# SH6_-_PCIe_ETHERNET.net
KiCad netlist of a schematic drawn in Altium Designer
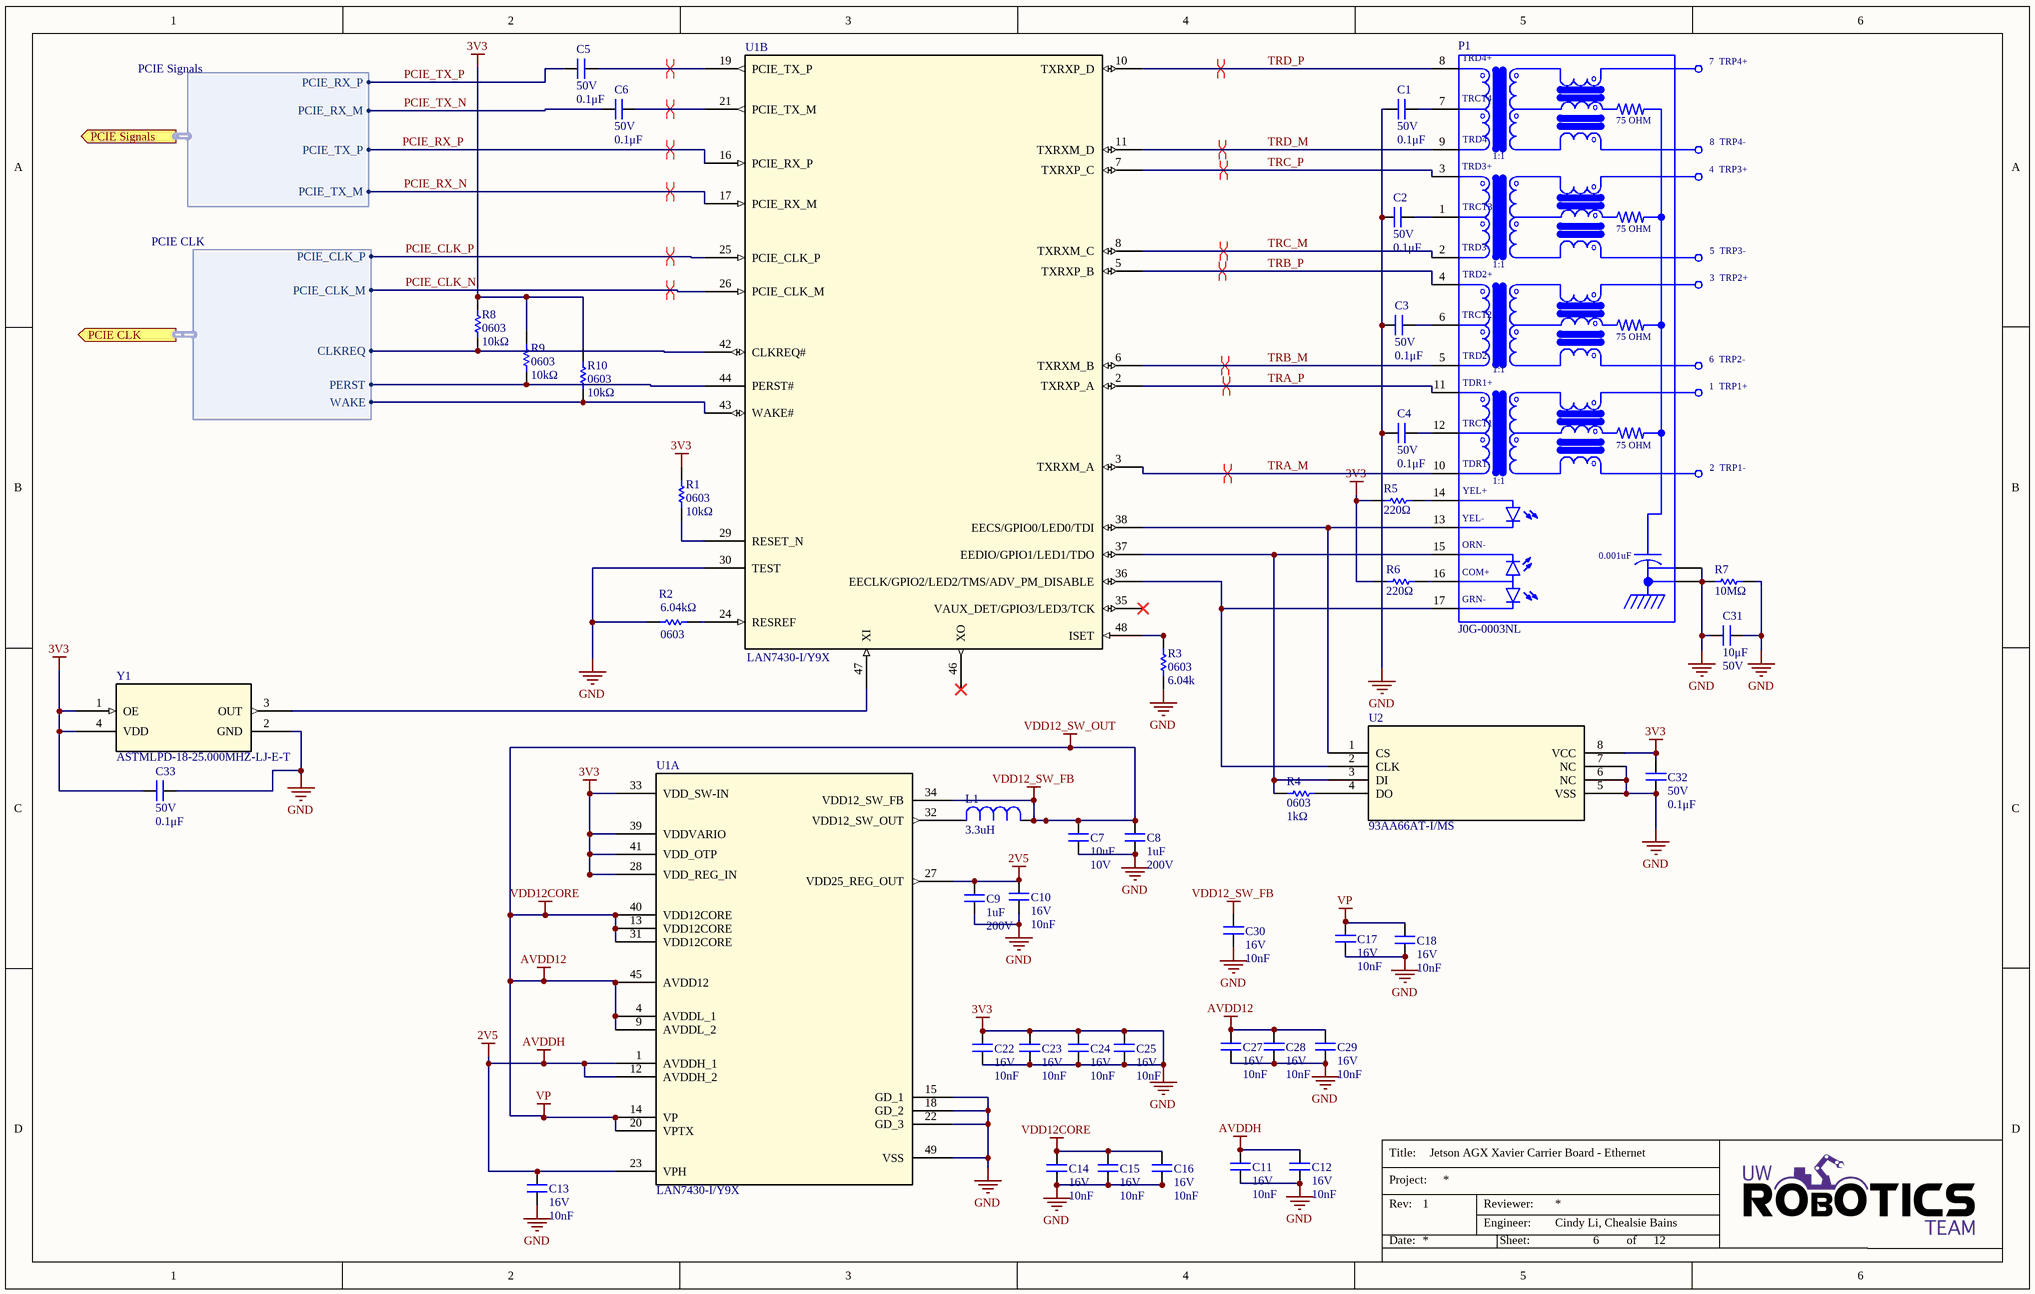
[diagram p0: SH6 - PCIe ETHERNET.SchDoc]

(export (version "E")
  (design (tool "Eeschema 10.0.6"))
  (components
    (comp (ref "C1")
      (value "0.1μF")
      (footprint "CAP0603")
      (description "CAP CER 0.1UF 50V X7R 0603")
      (fields (field (name "VOLTAGE RATING") "50V") (field (name "Comment") "CAP_0.1uF_50V_0603"))
      (libsource (lib "UWRT_Schematic_Library_2020") (part "CAP_0.1uF_50V_0603"))
    )
    (comp (ref "C2")
      (value "0.1μF")
      (footprint "CAP0603")
      (description "CAP CER 0.1UF 50V X7R 0603")
      (fields (field (name "VOLTAGE RATING") "50V") (field (name "Comment") "CAP_0.1uF_50V_0603"))
      (libsource (lib "UWRT_Schematic_Library_2020") (part "CAP_0.1uF_50V_0603"))
    )
    (comp (ref "C3")
      (value "0.1μF")
      (footprint "CAP0603")
      (description "CAP CER 0.1UF 50V X7R 0603")
      (fields (field (name "VOLTAGE RATING") "50V") (field (name "Comment") "CAP_0.1uF_50V_0603"))
      (libsource (lib "UWRT_Schematic_Library_2020") (part "CAP_0.1uF_50V_0603"))
    )
    (comp (ref "C4")
      (value "0.1μF")
      (footprint "CAP0603")
      (description "CAP CER 0.1UF 50V X7R 0603")
      (fields (field (name "VOLTAGE RATING") "50V") (field (name "Comment") "CAP_0.1uF_50V_0603"))
      (libsource (lib "UWRT_Schematic_Library_2020") (part "CAP_0.1uF_50V_0603"))
    )
    (comp (ref "C5")
      (value "0.1μF")
      (footprint "CAP0603")
      (description "CAP CER 0.1UF 50V X7R 0603")
      (fields (field (name "VOLTAGE RATING") "50V") (field (name "Comment") "CAP_0.1uF_50V_0603"))
      (libsource (lib "UWRT_Schematic_Library_2020") (part "CAP_0.1uF_50V_0603"))
    )
    (comp (ref "C6")
      (value "0.1μF")
      (footprint "CAP0603")
      (description "CAP CER 0.1UF 50V X7R 0603")
      (fields (field (name "VOLTAGE RATING") "50V") (field (name "Comment") "CAP_0.1uF_50V_0603"))
      (libsource (lib "UWRT_Schematic_Library_2020") (part "CAP_0.1uF_50V_0603"))
    )
    (comp (ref "C7")
      (value "10uF")
      (fields
        (field (name "MANUFACTURER") "Taiyo Yuden")
        (field (name "MANUFACTURER PART NUMBER") "LMK212AC6106MD-T")
        (field (name "VOLTAGE") "10V")
        (field (name "Comment") "CAP CER 10UF 10V X6S 0805")
      )
      (libsource (lib "UWRT_Schematic_Library_2020") (part "CAP CER 10UF 10V X6S 0805"))
    )
    (comp (ref "C8")
      (value "1uF")
      (footprint "CAP_CER_10000PF")
      (fields
        (field (name "MANUFACTURER") "Taiyo Yuden")
        (field (name "MANUFACTURER PART NUMBER") "GMK107BJ105MAHT")
        (field (name "VOLTAGE RATING") "200V")
        (field (name "Comment") "CAP_1uF_200V_0603")
      )
      (libsource (lib "UWRT_Schematic_Library_2020") (part "CAP_1uF_200V_0603"))
    )
    (comp (ref "C9")
      (value "1uF")
      (footprint "CAP_CER_10000PF")
      (fields
        (field (name "MANUFACTURER") "Taiyo Yuden")
        (field (name "MANUFACTURER PART NUMBER") "GMK107BJ105MAHT")
        (field (name "VOLTAGE RATING") "200V")
        (field (name "Comment") "CAP_1uF_200V_0603")
      )
      (libsource (lib "UWRT_Schematic_Library_2020") (part "CAP_1uF_200V_0603"))
    )
    (comp (ref "C10")
      (value "10nF")
      (footprint "CAP2012")
      (description "CAP CER 10000PF 16V X7R 0805")
      (fields (field (name "VOLTAGE RATING") "16V") (field (name "Comment") "CAP_10nF_16V_0805"))
      (libsource (lib "UWRT_Schematic_Library_2020") (part "CAP_10nF_16V_0805"))
    )
    (comp (ref "C11")
      (value "10nF")
      (footprint "CAP2012")
      (description "CAP CER 10000PF 16V X7R 0805")
      (fields (field (name "VOLTAGE RATING") "16V") (field (name "Comment") "CAP_10nF_16V_0805"))
      (libsource (lib "UWRT_Schematic_Library_2020") (part "CAP_10nF_16V_0805"))
    )
    (comp (ref "C12")
      (value "10nF")
      (footprint "CAP2012")
      (description "CAP CER 10000PF 16V X7R 0805")
      (fields (field (name "VOLTAGE RATING") "16V") (field (name "Comment") "CAP_10nF_16V_0805"))
      (libsource (lib "UWRT_Schematic_Library_2020") (part "CAP_10nF_16V_0805"))
    )
    (comp (ref "C13")
      (value "10nF")
      (footprint "CAP2012")
      (description "CAP CER 10000PF 16V X7R 0805")
      (fields (field (name "VOLTAGE RATING") "16V") (field (name "Comment") "CAP_10nF_16V_0805"))
      (libsource (lib "UWRT_Schematic_Library_2020") (part "CAP_10nF_16V_0805"))
    )
    (comp (ref "C14")
      (value "10nF")
      (footprint "CAP2012")
      (description "CAP CER 10000PF 16V X7R 0805")
      (fields (field (name "VOLTAGE RATING") "16V") (field (name "Comment") "CAP_10nF_16V_0805"))
      (libsource (lib "UWRT_Schematic_Library_2020") (part "CAP_10nF_16V_0805"))
    )
    (comp (ref "C15")
      (value "10nF")
      (footprint "CAP2012")
      (description "CAP CER 10000PF 16V X7R 0805")
      (fields (field (name "VOLTAGE RATING") "16V") (field (name "Comment") "CAP_10nF_16V_0805"))
      (libsource (lib "UWRT_Schematic_Library_2020") (part "CAP_10nF_16V_0805"))
    )
    (comp (ref "C16")
      (value "10nF")
      (footprint "CAP2012")
      (description "CAP CER 10000PF 16V X7R 0805")
      (fields (field (name "VOLTAGE RATING") "16V") (field (name "Comment") "CAP_10nF_16V_0805"))
      (libsource (lib "UWRT_Schematic_Library_2020") (part "CAP_10nF_16V_0805"))
    )
    (comp (ref "C17")
      (value "10nF")
      (footprint "CAP2012")
      (description "CAP CER 10000PF 16V X7R 0805")
      (fields (field (name "VOLTAGE RATING") "16V") (field (name "Comment") "CAP_10nF_16V_0805"))
      (libsource (lib "UWRT_Schematic_Library_2020") (part "CAP_10nF_16V_0805"))
    )
    (comp (ref "C18")
      (value "10nF")
      (footprint "CAP2012")
      (description "CAP CER 10000PF 16V X7R 0805")
      (fields (field (name "VOLTAGE RATING") "16V") (field (name "Comment") "CAP_10nF_16V_0805"))
      (libsource (lib "UWRT_Schematic_Library_2020") (part "CAP_10nF_16V_0805"))
    )
    (comp (ref "C22")
      (value "10nF")
      (footprint "CAP2012")
      (description "CAP CER 10000PF 16V X7R 0805")
      (fields (field (name "VOLTAGE RATING") "16V") (field (name "Comment") "CAP_10nF_16V_0805"))
      (libsource (lib "UWRT_Schematic_Library_2020") (part "CAP_10nF_16V_0805"))
    )
    (comp (ref "C23")
      (value "10nF")
      (footprint "CAP2012")
      (description "CAP CER 10000PF 16V X7R 0805")
      (fields (field (name "VOLTAGE RATING") "16V") (field (name "Comment") "CAP_10nF_16V_0805"))
      (libsource (lib "UWRT_Schematic_Library_2020") (part "CAP_10nF_16V_0805"))
    )
    (comp (ref "C24")
      (value "10nF")
      (footprint "CAP2012")
      (description "CAP CER 10000PF 16V X7R 0805")
      (fields (field (name "VOLTAGE RATING") "16V") (field (name "Comment") "CAP_10nF_16V_0805"))
      (libsource (lib "UWRT_Schematic_Library_2020") (part "CAP_10nF_16V_0805"))
    )
    (comp (ref "C25")
      (value "10nF")
      (footprint "CAP2012")
      (description "CAP CER 10000PF 16V X7R 0805")
      (fields (field (name "VOLTAGE RATING") "16V") (field (name "Comment") "CAP_10nF_16V_0805"))
      (libsource (lib "UWRT_Schematic_Library_2020") (part "CAP_10nF_16V_0805"))
    )
    (comp (ref "C27")
      (value "10nF")
      (footprint "CAP2012")
      (description "CAP CER 10000PF 16V X7R 0805")
      (fields (field (name "VOLTAGE RATING") "16V") (field (name "Comment") "CAP_10nF_16V_0805"))
      (libsource (lib "UWRT_Schematic_Library_2020") (part "CAP_10nF_16V_0805"))
    )
    (comp (ref "C28")
      (value "10nF")
      (footprint "CAP2012")
      (description "CAP CER 10000PF 16V X7R 0805")
      (fields (field (name "VOLTAGE RATING") "16V") (field (name "Comment") "CAP_10nF_16V_0805"))
      (libsource (lib "UWRT_Schematic_Library_2020") (part "CAP_10nF_16V_0805"))
    )
    (comp (ref "C29")
      (value "10nF")
      (footprint "CAP2012")
      (description "CAP CER 10000PF 16V X7R 0805")
      (fields (field (name "VOLTAGE RATING") "16V") (field (name "Comment") "CAP_10nF_16V_0805"))
      (libsource (lib "UWRT_Schematic_Library_2020") (part "CAP_10nF_16V_0805"))
    )
    (comp (ref "C30")
      (value "10nF")
      (footprint "CAP2012")
      (description "CAP CER 10000PF 16V X7R 0805")
      (fields (field (name "VOLTAGE RATING") "16V") (field (name "Comment") "CAP_10nF_16V_0805"))
      (libsource (lib "UWRT_Schematic_Library_2020") (part "CAP_10nF_16V_0805"))
    )
    (comp (ref "C31")
      (value "10μF")
      (footprint "CAP1206")
      (description "CAP CER 10UF 50V X5R 1206")
      (fields (field (name "VOLTAGE RATING") "50V") (field (name "Comment") "CAP_10uF_50V_1206"))
      (libsource (lib "UWRT_Schematic_Library_2020") (part "CAP_10uF_50V_1206"))
    )
    (comp (ref "C32")
      (value "0.1μF")
      (footprint "CAP0603")
      (description "CAP CER 0.1UF 50V X7R 0603")
      (fields (field (name "VOLTAGE RATING") "50V") (field (name "Comment") "CAP_0.1uF_50V_0603"))
      (libsource (lib "UWRT_Schematic_Library_2020") (part "CAP_0.1uF_50V_0603"))
    )
    (comp (ref "C33")
      (value "0.1μF")
      (footprint "CAP0603")
      (description "CAP CER 0.1UF 50V X7R 0603")
      (fields (field (name "VOLTAGE RATING") "50V") (field (name "Comment") "CAP_0.1uF_50V_0603"))
      (libsource (lib "UWRT_Schematic_Library_2020") (part "CAP_0.1uF_50V_0603"))
    )
    (comp (ref "L1")
      (value "IND_3.3uH")
      (footprint "IND_BOURNS_SRN6045")
      (description "FIXED INDUCTOR 3.3UH SMD")
      (fields (field (name "INDUCTANCE") "3.3uH"))
      (libsource (lib "UWRT_Schematic_Library_2020") (part "IND_3.3uH"))
    )
    (comp (ref "P1")
      (value "J0G-0003NL")
      (footprint "SnapEDApcb:PULSE_J0G-0003NL")
      (description "1 Port RJ45 Magjack Connector Through Hole 10/100/1000 Base-T, AutoMDIX")
      (fields (field (name "DIGI-KEY_PART_NUMBER") "553-1852-ND") (field (name "MF") "Pulse Electronics"))
      (libsource (lib "UWRT_Schematic_Library_2020") (part "J0G-0003NL"))
    )
    (comp (ref "R1")
      (value "10kΩ")
      (footprint "RESC0603")
      (description "RES 10K OHM 5% 1/10W 0603")
      (fields (field (name "PACKAGE/FOOTPRINT") "0603") (field (name "Comment") "RES_10kΩ_0603_5%"))
      (libsource (lib "UWRT_Schematic_Library_2020") (part "RES_10kΩ_0603_5%"))
    )
    (comp (ref "R2")
      (value "~")
      (footprint "RESC1608X55N:RESC1608X55N")
      (description "RES 0603 200 OHM 1/10W 1% SMD")
      (fields (field (name "MP") "SFR03EZPF2000"))
      (libsource (lib "UWRT_Schematic_Library_2020") (part "RES_200Ω"))
    )
    (comp (ref "R3")
      (value "6.04k")
      (footprint "RES0603")
      (description "RES 6.04K OHM 1% 1/10W 0603")
      (fields (field (name "PACKAGE/FOOTPRINT") "0603") (field (name "Comment") "RES_6.04kΩ_0603_1%"))
      (libsource (lib "UWRT_Schematic_Library_2020") (part "RES_6.04kΩ_0603_1%"))
    )
    (comp (ref "R4")
      (value "1kΩ")
      (footprint "RESC0603")
      (description "RES 1K OHM 5% 1/10W 0603")
      (fields (field (name "PACKAGE/FOOTPRINT") "0603") (field (name "Comment") "RES_1kΩ_0603_5%"))
      (libsource (lib "UWRT_Schematic_Library_2020") (part "RES_1kΩ_0603_5%"))
    )
    (comp (ref "R5")
      (value "220Ω")
      (footprint "RESC0603")
      (description "RES 220 OHM 5% 1/10W 0603")
      (fields (field (name "Comment") "RES_220Ω_0603"))
      (libsource (lib "UWRT_Schematic_Library_2020") (part "RES_220Ω_0603_5%"))
    )
    (comp (ref "R6")
      (value "220Ω")
      (footprint "RESC0603")
      (description "RES 220 OHM 5% 1/10W 0603")
      (fields (field (name "Comment") "RES_220Ω_0603"))
      (libsource (lib "UWRT_Schematic_Library_2020") (part "RES_220Ω_0603_5%"))
    )
    (comp (ref "R7")
      (value "10MΩ")
      (footprint "RES0603")
      (description "RES 10M OHM 5% 1/10W 0603")
      (fields (field (name "Comment") "RES_10MΩ_0603"))
      (libsource (lib "UWRT_Schematic_Library_2020") (part "RES_10MΩ_0603_5%"))
    )
    (comp (ref "R8")
      (value "10kΩ")
      (footprint "RES0603")
      (description "RES 10K OHM 5% 1/10W 0603")
      (fields (field (name "PACKAGE/FOOTPRINT") "0603") (field (name "Comment") "RES_10kΩ_0603_5%"))
      (libsource (lib "UWRT_Schematic_Library_2020") (part "RES_10kΩ_0603_5%"))
    )
    (comp (ref "R9")
      (value "10kΩ")
      (footprint "RES0603")
      (description "RES 10K OHM 5% 1/10W 0603")
      (fields (field (name "PACKAGE/FOOTPRINT") "0603") (field (name "Comment") "RES_10kΩ_0603_5%"))
      (libsource (lib "UWRT_Schematic_Library_2020") (part "RES_10kΩ_0603_5%"))
    )
    (comp (ref "R10")
      (value "10kΩ")
      (footprint "RES0603")
      (description "RES 10K OHM 5% 1/10W 0603")
      (fields (field (name "PACKAGE/FOOTPRINT") "0603") (field (name "Comment") "RES_10kΩ_0603_5%"))
      (libsource (lib "UWRT_Schematic_Library_2020") (part "RES_10kΩ_0603_5%"))
    )
    (comp (ref "U1")
      (value "LAN7430-I/Y9X")
      (footprint "SQFN48_MCH")
      (fields (field (name "COPYRIGHT") "Copyright (C) 2018 Accelerated Designs. All rights reserved"))
      (libsource (lib "UWRT_Schematic_Library_2020") (part "LAN7430-I/Y9X"))
    )
    (comp (ref "U2")
      (value "93AA66AT-I/MS")
      (footprint "MSOP8_MC_MCH")
      (description "No Description Available")
      (fields (field (name "COPYRIGHT") "Copyright (C) 2018 Accelerated Designs. All rights reserved"))
      (libsource (lib "UWRT_Schematic_Library_2020") (part "93AA66AT-I/MS"))
    )
    (comp (ref "Y1")
      (value "ASTMLPD-18-25.000MHZ-LJ-E-T")
      (footprint "ASTMLPE_ABR")
      (description "Oscillator")
      (libsource (lib "UWRT_Schematic_Library_2020") (part "ASTMLPD-18-25.000MHZ-LJ-E-T"))
    )
  )
  (nets
    (net (code "4") (name "/PCIE_CLK_N") (class "Default")
      (node (ref "U1") (pin "26") (pinfunction "PCIE_CLK_M_26") (pintype "input"))
    )
    (net (code "5") (name "/PCIE_CLK_P") (class "Default")
      (node (ref "U1") (pin "25") (pinfunction "PCIE_CLK_P_25") (pintype "input"))
    )
    (net (code "6") (name "/PCIE_RX_N") (class "Default")
      (node (ref "U1") (pin "17") (pinfunction "PCIE_RX_M_17") (pintype "input"))
    )
    (net (code "7") (name "/PCIE_RX_P") (class "Default")
      (node (ref "U1") (pin "16") (pinfunction "PCIE_RX_P_16") (pintype "input"))
    )
    (net (code "8") (name "/PCIE_TX_N") (class "Default")
      (node (ref "C6") (pin "1") (pinfunction "1_1") (pintype "passive"))
    )
    (net (code "9") (name "/PCIE_TX_P") (class "Default")
      (node (ref "C5") (pin "1") (pinfunction "1_1") (pintype "passive"))
    )
    (net (code "10") (name "/TRA_M") (class "Default")
      (node (ref "P1") (pin "10") (pinfunction "TDR1-_10") (pintype "passive"))
      (node (ref "U1") (pin "3") (pinfunction "TXRXM_A_3") (pintype "bidirectional"))
    )
    (net (code "11") (name "/TRA_P") (class "Default")
      (node (ref "P1") (pin "11") (pinfunction "TDR1+_11") (pintype "passive"))
      (node (ref "U1") (pin "2") (pinfunction "TXRXP_A_2") (pintype "bidirectional"))
    )
    (net (code "12") (name "/TRB_M") (class "Default")
      (node (ref "P1") (pin "5") (pinfunction "TRD2-_5") (pintype "passive"))
      (node (ref "U1") (pin "6") (pinfunction "TXRXM_B_6") (pintype "bidirectional"))
    )
    (net (code "13") (name "/TRB_P") (class "Default")
      (node (ref "P1") (pin "4") (pinfunction "TRD2+_4") (pintype "passive"))
      (node (ref "U1") (pin "5") (pinfunction "TXRXP_B_5") (pintype "bidirectional"))
    )
    (net (code "14") (name "/TRC_M") (class "Default")
      (node (ref "P1") (pin "2") (pinfunction "TRD3-_2") (pintype "passive"))
      (node (ref "U1") (pin "8") (pinfunction "TXRXM_C_8") (pintype "bidirectional"))
    )
    (net (code "15") (name "/TRC_P") (class "Default")
      (node (ref "P1") (pin "3") (pinfunction "TRD3+_3") (pintype "passive"))
      (node (ref "U1") (pin "7") (pinfunction "TXRXP_C_7") (pintype "bidirectional"))
    )
    (net (code "16") (name "/TRD_M") (class "Default")
      (node (ref "P1") (pin "9") (pinfunction "TRD4-_9") (pintype "passive"))
      (node (ref "U1") (pin "11") (pinfunction "TXRXM_D_11") (pintype "bidirectional"))
    )
    (net (code "17") (name "/TRD_P") (class "Default")
      (node (ref "P1") (pin "8") (pinfunction "TRD4+_8") (pintype "passive"))
      (node (ref "U1") (pin "10") (pinfunction "TXRXP_D_10") (pintype "bidirectional"))
    )
    (net (code "20") (name "2V5") (class "Default")
      (node (ref "C10") (pin "2") (pinfunction "2_2") (pintype "passive"))
      (node (ref "C11") (pin "2") (pinfunction "2_2") (pintype "passive"))
      (node (ref "C12") (pin "2") (pinfunction "2_2") (pintype "passive"))
      (node (ref "C13") (pin "2") (pinfunction "2_2") (pintype "passive"))
      (node (ref "C9") (pin "2") (pinfunction "2_2") (pintype "passive"))
      (node (ref "U1") (pin "1") (pinfunction "AVDDH_1_1") (pintype "power_in"))
      (node (ref "U1") (pin "12") (pinfunction "AVDDH_2_12") (pintype "power_in"))
      (node (ref "U1") (pin "23") (pinfunction "VPH_23") (pintype "power_in"))
      (node (ref "U1") (pin "27") (pinfunction "VDD25_REG_OUT_27") (pintype "output"))
    )
    (net (code "21") (name "3V3") (class "Default")
      (node (ref "C1") (pin "1") (pinfunction "1_1") (pintype "passive"))
      (node (ref "C10") (pin "1") (pinfunction "1_1") (pintype "passive"))
      (node (ref "C11") (pin "1") (pinfunction "1_1") (pintype "passive"))
      (node (ref "C12") (pin "1") (pinfunction "1_1") (pintype "passive"))
      (node (ref "C13") (pin "1") (pinfunction "1_1") (pintype "passive"))
      (node (ref "C14") (pin "1") (pinfunction "1_1") (pintype "passive"))
      (node (ref "C15") (pin "1") (pinfunction "1_1") (pintype "passive"))
      (node (ref "C16") (pin "1") (pinfunction "1_1") (pintype "passive"))
      (node (ref "C17") (pin "1") (pinfunction "1_1") (pintype "passive"))
      (node (ref "C18") (pin "1") (pinfunction "1_1") (pintype "passive"))
      (node (ref "C2") (pin "1") (pinfunction "1_1") (pintype "passive"))
      (node (ref "C22") (pin "1") (pinfunction "1_1") (pintype "passive"))
      (node (ref "C22") (pin "2") (pinfunction "2_2") (pintype "passive"))
      (node (ref "C23") (pin "1") (pinfunction "1_1") (pintype "passive"))
      (node (ref "C23") (pin "2") (pinfunction "2_2") (pintype "passive"))
      (node (ref "C24") (pin "1") (pinfunction "1_1") (pintype "passive"))
      (node (ref "C24") (pin "2") (pinfunction "2_2") (pintype "passive"))
      (node (ref "C25") (pin "1") (pinfunction "1_1") (pintype "passive"))
      (node (ref "C25") (pin "2") (pinfunction "2_2") (pintype "passive"))
      (node (ref "C27") (pin "1") (pinfunction "1_1") (pintype "passive"))
      (node (ref "C28") (pin "1") (pinfunction "1_1") (pintype "passive"))
      (node (ref "C29") (pin "1") (pinfunction "1_1") (pintype "passive"))
      (node (ref "C3") (pin "1") (pinfunction "1_1") (pintype "passive"))
      (node (ref "C30") (pin "1") (pinfunction "1_1") (pintype "passive"))
      (node (ref "C31") (pin "1") (pinfunction "1_1") (pintype "passive"))
      (node (ref "C31") (pin "2") (pinfunction "2_2") (pintype "passive"))
      (node (ref "C32") (pin "1") (pinfunction "1_1") (pintype "passive"))
      (node (ref "C32") (pin "2") (pinfunction "2_2") (pintype "passive"))
      (node (ref "C33") (pin "1") (pinfunction "1_1") (pintype "passive"))
      (node (ref "C33") (pin "2") (pinfunction "2_2") (pintype "passive"))
      (node (ref "C4") (pin "1") (pinfunction "1_1") (pintype "passive"))
      (node (ref "C7") (pin "1") (pinfunction "1_1") (pintype "passive"))
      (node (ref "C8") (pin "1") (pinfunction "1_1") (pintype "passive"))
      (node (ref "C9") (pin "1") (pinfunction "1_1") (pintype "passive"))
      (node (ref "P1") (pin "SH1") (pinfunction "SHIELD_SH1") (pintype "power_in"))
      (node (ref "P1") (pin "SH2") (pinfunction "SHIELD_SH2") (pintype "power_in"))
      (node (ref "R1") (pin "2") (pinfunction "2_2") (pintype "passive"))
      (node (ref "R10") (pin "2") (pinfunction "2_2") (pintype "passive"))
      (node (ref "R2") (pin "1") (pinfunction "1_1") (pintype "passive"))
      (node (ref "R3") (pin "2") (pinfunction "2_2") (pintype "passive"))
      (node (ref "R5") (pin "1") (pinfunction "1_1") (pintype "passive"))
      (node (ref "R6") (pin "1") (pinfunction "1_1") (pintype "passive"))
      (node (ref "R7") (pin "1") (pinfunction "1_1") (pintype "passive"))
      (node (ref "R7") (pin "2") (pinfunction "2_2") (pintype "passive"))
      (node (ref "R8") (pin "2") (pinfunction "2_2") (pintype "passive"))
      (node (ref "R9") (pin "2") (pinfunction "2_2") (pintype "passive"))
      (node (ref "U1") (pin "15") (pinfunction "GD_1_15") (pintype "power_in"))
      (node (ref "U1") (pin "18") (pinfunction "GD_2_18") (pintype "power_in"))
      (node (ref "U1") (pin "22") (pinfunction "GD_3_22") (pintype "power_in"))
      (node (ref "U1") (pin "28") (pinfunction "VDD_REG_IN_28") (pintype "power_in"))
      (node (ref "U1") (pin "30") (pinfunction "TEST_30") (pintype "passive"))
      (node (ref "U1") (pin "33") (pinfunction "VDD_SW-IN_33") (pintype "power_in"))
      (node (ref "U1") (pin "39") (pinfunction "VDDVARIO_39") (pintype "power_in"))
      (node (ref "U1") (pin "41") (pinfunction "VDD_OTP_41") (pintype "power_in"))
      (node (ref "U1") (pin "49") (pinfunction "VSS_49") (pintype "passive"))
      (node (ref "U2") (pin "5") (pinfunction "VSS_5") (pintype "passive"))
      (node (ref "U2") (pin "6") (pinfunction "NC_6") (pintype "passive"))
      (node (ref "U2") (pin "7") (pinfunction "NC_7") (pintype "passive"))
      (node (ref "U2") (pin "8") (pinfunction "VCC_8") (pintype "passive"))
      (node (ref "Y1") (pin "1") (pinfunction "OE_1") (pintype "input"))
      (node (ref "Y1") (pin "2") (pinfunction "GND_2") (pintype "passive"))
      (node (ref "Y1") (pin "4") (pinfunction "VDD_4") (pintype "power_in"))
    )
    (net (code "22") (name "AVDD12") (class "Default")
      (node (ref "C14") (pin "2") (pinfunction "2_2") (pintype "passive"))
      (node (ref "C15") (pin "2") (pinfunction "2_2") (pintype "passive"))
      (node (ref "C16") (pin "2") (pinfunction "2_2") (pintype "passive"))
      (node (ref "C17") (pin "2") (pinfunction "2_2") (pintype "passive"))
      (node (ref "C18") (pin "2") (pinfunction "2_2") (pintype "passive"))
      (node (ref "C27") (pin "2") (pinfunction "2_2") (pintype "passive"))
      (node (ref "C28") (pin "2") (pinfunction "2_2") (pintype "passive"))
      (node (ref "C29") (pin "2") (pinfunction "2_2") (pintype "passive"))
      (node (ref "C7") (pin "2") (pinfunction "2_2") (pintype "passive"))
      (node (ref "C8") (pin "2") (pinfunction "2_2") (pintype "passive"))
      (node (ref "L1") (pin "1") (pinfunction "1_1") (pintype "passive"))
      (node (ref "U1") (pin "13") (pinfunction "VDD12CORE_13") (pintype "power_in"))
      (node (ref "U1") (pin "14") (pinfunction "VP_14") (pintype "power_in"))
      (node (ref "U1") (pin "20") (pinfunction "VPTX_20") (pintype "power_in"))
      (node (ref "U1") (pin "31") (pinfunction "VDD12CORE_31") (pintype "power_in"))
      (node (ref "U1") (pin "34") (pinfunction "VDD12_SW_FB_34") (pintype "power_in"))
      (node (ref "U1") (pin "4") (pinfunction "AVDDL_1_4") (pintype "power_in"))
      (node (ref "U1") (pin "40") (pinfunction "VDD12CORE_40") (pintype "power_in"))
      (node (ref "U1") (pin "45") (pinfunction "AVDD12_45") (pintype "power_in"))
      (node (ref "U1") (pin "9") (pinfunction "AVDDL_2_9") (pintype "power_in"))
    )
    (net (code "23") (name "Net-(P1-COM+)") (class "Default")
      (node (ref "P1") (pin "16") (pinfunction "COM+_16") (pintype "passive"))
      (node (ref "R6") (pin "2") (pinfunction "2_2") (pintype "passive"))
    )
    (net (code "24") (name "Net-(P1-GRN-)") (class "Default")
      (node (ref "P1") (pin "17") (pinfunction "GRN-_17") (pintype "passive"))
      (node (ref "U1") (pin "36") (pinfunction "EECLK/GPIO2/LED2/TMS/ADV_PM_DISABLE_36") (pintype "bidirectional"))
      (node (ref "U2") (pin "2") (pinfunction "CLK_2") (pintype "passive"))
    )
    (net (code "25") (name "Net-(P1-ORN-)") (class "Default")
      (node (ref "P1") (pin "15") (pinfunction "ORN-_15") (pintype "passive"))
      (node (ref "R4") (pin "1") (pinfunction "1_1") (pintype "passive"))
      (node (ref "U1") (pin "37") (pinfunction "EEDIO/GPIO1/LED1/TDO_37") (pintype "bidirectional"))
      (node (ref "U2") (pin "3") (pinfunction "DI_3") (pintype "passive"))
    )
    (net (code "26") (name "Net-(P1-TRCT1)") (class "Default")
      (node (ref "C4") (pin "2") (pinfunction "2_2") (pintype "passive"))
      (node (ref "P1") (pin "12") (pinfunction "TRCT1_12") (pintype "passive"))
    )
    (net (code "27") (name "Net-(P1-TRCT2)") (class "Default")
      (node (ref "C3") (pin "2") (pinfunction "2_2") (pintype "passive"))
      (node (ref "P1") (pin "6") (pinfunction "TRCT2_6") (pintype "passive"))
    )
    (net (code "28") (name "Net-(P1-TRCT3)") (class "Default")
      (node (ref "C2") (pin "2") (pinfunction "2_2") (pintype "passive"))
      (node (ref "P1") (pin "1") (pinfunction "TRCT3_1") (pintype "passive"))
    )
    (net (code "29") (name "Net-(P1-TRCT4)") (class "Default")
      (node (ref "C1") (pin "2") (pinfunction "2_2") (pintype "passive"))
      (node (ref "P1") (pin "7") (pinfunction "TRCT4_7") (pintype "passive"))
    )
    (net (code "30") (name "Net-(P1-YEL+)") (class "Default")
      (node (ref "P1") (pin "14") (pinfunction "YEL+_14") (pintype "passive"))
      (node (ref "R5") (pin "2") (pinfunction "2_2") (pintype "passive"))
    )
    (net (code "31") (name "Net-(P1-YEL-)") (class "Default")
      (node (ref "P1") (pin "13") (pinfunction "YEL-_13") (pintype "passive"))
      (node (ref "U1") (pin "38") (pinfunction "EECS/GPIO0/LED0/TDI_38") (pintype "bidirectional"))
      (node (ref "U2") (pin "1") (pinfunction "CS_1") (pintype "passive"))
    )
    (net (code "32") (name "Net-(U1A-VDD12_SW_OUT)") (class "Default")
      (node (ref "L1") (pin "2") (pinfunction "2_2") (pintype "passive"))
      (node (ref "U1") (pin "32") (pinfunction "VDD12_SW_OUT_32") (pintype "output"))
    )
    (net (code "33") (name "Net-(U1B-CLKREQ#)") (class "Default")
      (node (ref "R8") (pin "1") (pinfunction "1_1") (pintype "passive"))
      (node (ref "U1") (pin "42") (pinfunction "CLKREQ#_42") (pintype "bidirectional"))
    )
    (net (code "34") (name "Net-(U1B-ISET)") (class "Default")
      (node (ref "R3") (pin "1") (pinfunction "1_1") (pintype "passive"))
      (node (ref "U1") (pin "48") (pinfunction "ISET_48") (pintype "input"))
    )
    (net (code "35") (name "Net-(U1B-PCIE_TX_M)") (class "Default")
      (node (ref "C6") (pin "2") (pinfunction "2_2") (pintype "passive"))
      (node (ref "U1") (pin "21") (pinfunction "PCIE_TX_M_21") (pintype "output"))
    )
    (net (code "36") (name "Net-(U1B-PCIE_TX_P)") (class "Default")
      (node (ref "C5") (pin "2") (pinfunction "2_2") (pintype "passive"))
      (node (ref "U1") (pin "19") (pinfunction "PCIE_TX_P_19") (pintype "output"))
    )
    (net (code "37") (name "Net-(U1B-PERST#)") (class "Default")
      (node (ref "R9") (pin "1") (pinfunction "1_1") (pintype "passive"))
      (node (ref "U1") (pin "44") (pinfunction "PERST#_44") (pintype "passive"))
    )
    (net (code "38") (name "Net-(U1B-RESET_N)") (class "Default")
      (node (ref "R1") (pin "1") (pinfunction "1_1") (pintype "passive"))
      (node (ref "U1") (pin "29") (pinfunction "RESET_N_29") (pintype "passive"))
    )
    (net (code "39") (name "Net-(U1B-RESREF)") (class "Default")
      (node (ref "R2") (pin "2") (pinfunction "2_2") (pintype "passive"))
      (node (ref "U1") (pin "24") (pinfunction "RESREF_24") (pintype "input"))
    )
    (net (code "40") (name "Net-(U1B-WAKE#)") (class "Default")
      (node (ref "R10") (pin "1") (pinfunction "1_1") (pintype "passive"))
      (node (ref "U1") (pin "43") (pinfunction "WAKE#_43") (pintype "bidirectional"))
    )
    (net (code "41") (name "Net-(U1B-XI)") (class "Default")
      (node (ref "U1") (pin "47") (pinfunction "XI_47") (pintype "input"))
      (node (ref "Y1") (pin "3") (pinfunction "OUT_3") (pintype "output"))
    )
    (net (code "42") (name "Net-(U2-DO)") (class "Default")
      (node (ref "R4") (pin "2") (pinfunction "2_2") (pintype "passive"))
      (node (ref "U2") (pin "4") (pinfunction "DO_4") (pintype "passive"))
    )
    (net (code "43") (name "unconnected-(C30-Pad2)") (class "Default")
      (node (ref "C30") (pin "2") (pinfunction "2_2") (pintype "passive"))
    )
    (net (code "44") (name "unconnected-(U1B-VAUX_DET{slash}GPIO3{slash}LED3{slash}TCK-Pad35)") (class "Default")
      (node (ref "U1") (pin "35") (pinfunction "VAUX_DET/GPIO3/LED3/TCK_35") (pintype "bidirectional+no_connect"))
    )
    (net (code "45") (name "unconnected-(U1B-XO-Pad46)") (class "Default")
      (node (ref "U1") (pin "46") (pinfunction "XO_46") (pintype "output+no_connect"))
    )
  )
)
